# DC_DC.net
KiCad netlist of a schematic drawn in Altium Designer
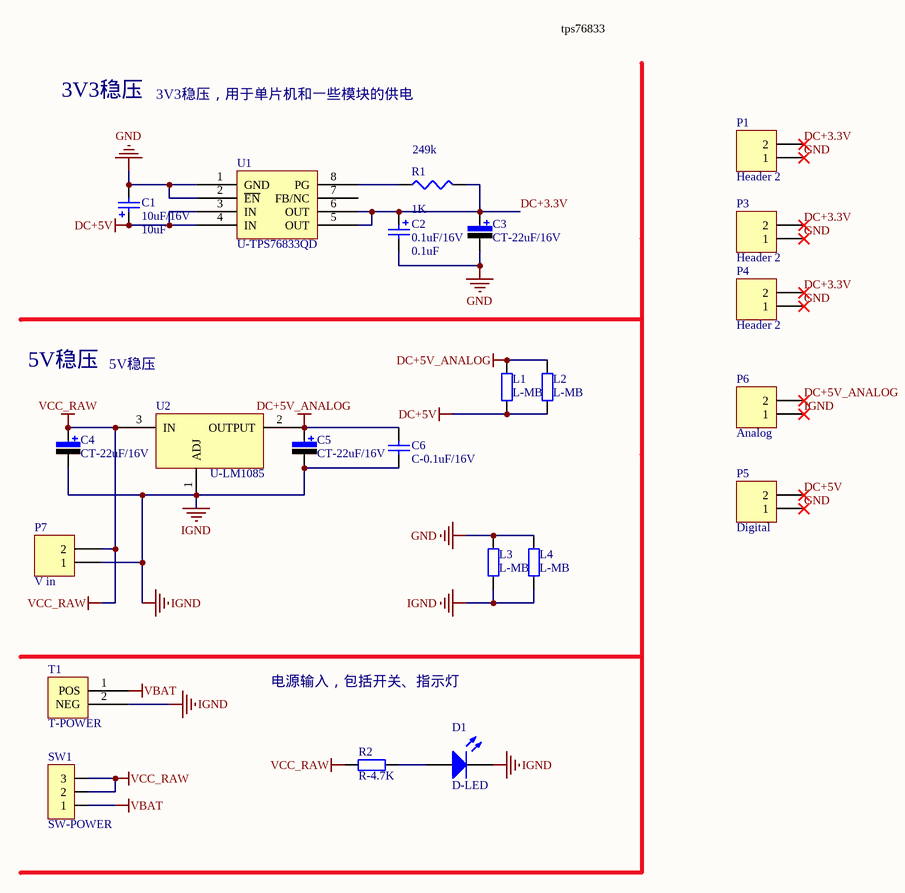
[diagram p0: DC_DC.SchDoc]

(export (version "E")
  (design (tool "Eeschema 10.0.6"))
  (components
    (comp (ref "C1")
      (value "10uF/16V")
      (footprint "CAP-1206")
      (description "Polarized Capacitor (Axial)")
      (fields (field (name "ALTIUM_VALUE") "10uF") (field (name "PUBLISHER") "Altium Limited"))
      (libsource (lib "Miscellaneous Devices") (part "Cap Pol2"))
    )
    (comp (ref "C2")
      (value "0.1uF/16V")
      (footprint "ZhiXingDoubleWing:CAP-1206")
      (description "Polarized Capacitor (Axial)")
      (fields (field (name "ALTIUM_VALUE") "0.1uF") (field (name "PUBLISHER") "Altium Limited"))
      (libsource (lib "Miscellaneous Devices") (part "Cap Pol2"))
    )
    (comp (ref "C3")
      (value "CT-22uF/16V")
      (footprint "CAP-3528")
      (description "钽电容")
      (fields (field (name "PUBLISHER") "Altium Limited"))
      (libsource (lib "Miscellaneous Devices") (part "Cap-Pol-A"))
    )
    (comp (ref "C4")
      (value "CT-22uF/16V")
      (footprint "CAP-3528")
      (description "钽电容")
      (fields (field (name "PUBLISHER") "Altium Limited"))
      (libsource (lib "fszhang") (part "Cap-Pol-A"))
    )
    (comp (ref "C5")
      (value "CT-22uF/16V")
      (footprint "CAP-3528")
      (description "钽电容")
      (fields (field (name "PUBLISHER") "Altium Limited"))
      (libsource (lib "fszhang") (part "Cap-Pol-A"))
    )
    (comp (ref "C6")
      (value "C-0.1uF/16V")
      (footprint "0603-1")
      (description "Capacitor")
      (fields (field (name "PUBLISHER") "Altium Limited"))
      (libsource (lib "Miscellaneous Devices") (part "Cap"))
    )
    (comp (ref "D1")
      (value "D-LED")
      (footprint "0603-1")
      (description "Typical RED, GREEN, YELLOW, AMBER GaAs LED")
      (fields (field (name "PUBLISHER") "Altium Limited"))
      (libsource (lib "FREESCALE") (part "LED2"))
    )
    (comp (ref "L1")
      (value "L-MB")
      (footprint "0603-1")
      (description "Resistor")
      (fields (field (name "PUBLISHER") "Altium Limited"))
      (libsource (lib "2014-SmartCar-DianCi(V4.0)") (part "Res2"))
    )
    (comp (ref "L2")
      (value "L-MB")
      (footprint "0603-1")
      (description "Resistor")
      (fields (field (name "PUBLISHER") "Altium Limited"))
      (libsource (lib "2014-SmartCar-DianCi(V4.0)") (part "Res2"))
    )
    (comp (ref "L3")
      (value "L-MB")
      (footprint "0603-1")
      (description "Resistor")
      (fields (field (name "PUBLISHER") "Altium Limited"))
      (libsource (lib "") (part "Res2_1"))
    )
    (comp (ref "L4")
      (value "L-MB")
      (footprint "0603-1")
      (description "Resistor")
      (fields (field (name "PUBLISHER") "Altium Limited"))
      (libsource (lib "") (part "Res2_1"))
    )
    (comp (ref "P1")
      (value "Header 2")
      (footprint "HDR1X2")
      (description "Header, 2-Pin")
      (fields (field (name "PUBLISHER") "Altium Limited"))
      (libsource (lib "Miscellaneous Connectors") (part "Header 2"))
    )
    (comp (ref "P3")
      (value "Header 2")
      (footprint "HDR1X2")
      (description "Header, 2-Pin")
      (fields (field (name "PUBLISHER") "Altium Limited"))
      (libsource (lib "Miscellaneous Connectors") (part "Header 2"))
    )
    (comp (ref "P4")
      (value "Header 2")
      (footprint "HDR1X2")
      (description "Header, 2-Pin")
      (fields (field (name "PUBLISHER") "Altium Limited"))
      (libsource (lib "Miscellaneous Connectors") (part "Header 2"))
    )
    (comp (ref "P5")
      (value "Digital")
      (footprint "HDR1X2")
      (description "Header, 2-Pin")
      (fields (field (name "PUBLISHER") "Altium Limited"))
      (libsource (lib "Miscellaneous Connectors") (part "Header 2"))
    )
    (comp (ref "P6")
      (value "Analog")
      (footprint "HDR1X2")
      (description "Header, 2-Pin")
      (fields (field (name "PUBLISHER") "Altium Limited"))
      (libsource (lib "Miscellaneous Connectors") (part "Header 2"))
    )
    (comp (ref "P7")
      (value "V in")
      (footprint "HDR1X2")
      (description "Header, 2-Pin")
      (fields (field (name "PUBLISHER") "Altium Limited"))
      (libsource (lib "Miscellaneous Connectors") (part "Header 2"))
    )
    (comp (ref "R1")
      (value "249k")
      (footprint "0603-1")
      (description "Resistor")
      (fields (field (name "ALTIUM_VALUE") "1K") (field (name "PUBLISHER") "Altium Limited"))
      (libsource (lib "Miscellaneous Devices") (part "Res3"))
    )
    (comp (ref "R2")
      (value "R-4.7K")
      (footprint "0603-1")
      (description "Resistor")
      (fields (field (name "PUBLISHER") "Altium Limited"))
      (libsource (lib "Miscellaneous Devices") (part "Res2"))
    )
    (comp (ref "SW1")
      (value "SW-POWER")
      (footprint "SWITCH_A4")
      (libsource (lib "FREESCALE") (part "大三端电源开关"))
    )
    (comp (ref "T1") (value "T-POWER") (footprint "PWR_HDR") (libsource (lib "fszhang") (part "PWR_HDR")))
    (comp (ref "U1") (value "U-TPS76833QD") (footprint "SOIC8") (libsource (lib "fszhang") (part "TPS76850")))
    (comp (ref "U2") (value "U-LM1085") (footprint "TO263-3") (libsource (lib "fszhang") (part "LM1085")))
  )
  (nets
    (net (code "1") (name "/DC+3.3V") (class "Default")
      (node (ref "C2") (pin "1") (pinfunction "1_1") (pintype "passive"))
      (node (ref "C3") (pin "1") (pinfunction "1_1") (pintype "passive"))
      (node (ref "P1") (pin "2") (pinfunction "2_2") (pintype "passive"))
      (node (ref "P3") (pin "2") (pinfunction "2_2") (pintype "passive"))
      (node (ref "P4") (pin "2") (pinfunction "2_2") (pintype "passive"))
      (node (ref "R1") (pin "2") (pinfunction "2_2") (pintype "passive"))
      (node (ref "U1") (pin "5") (pinfunction "OUT_5") (pintype "passive"))
      (node (ref "U1") (pin "6") (pinfunction "OUT_6") (pintype "passive"))
    )
    (net (code "2") (name "DC+5V") (class "Default")
      (node (ref "C1") (pin "1") (pinfunction "1_1") (pintype "passive"))
      (node (ref "L1") (pin "1") (pinfunction "1_1") (pintype "passive"))
      (node (ref "L2") (pin "1") (pinfunction "1_1") (pintype "passive"))
      (node (ref "P5") (pin "2") (pinfunction "2_2") (pintype "passive"))
      (node (ref "U1") (pin "3") (pinfunction "IN_3") (pintype "passive"))
      (node (ref "U1") (pin "4") (pinfunction "IN_4") (pintype "passive"))
    )
    (net (code "3") (name "DC+5V_ANALOG") (class "Default")
      (node (ref "C5") (pin "1") (pinfunction "1_1") (pintype "passive"))
      (node (ref "C6") (pin "2") (pinfunction "2_2") (pintype "passive"))
      (node (ref "L1") (pin "2") (pinfunction "2_2") (pintype "passive"))
      (node (ref "L2") (pin "2") (pinfunction "2_2") (pintype "passive"))
      (node (ref "P6") (pin "2") (pinfunction "2_2") (pintype "passive"))
      (node (ref "U2") (pin "2") (pinfunction "OUTPUT_2") (pintype "passive"))
    )
    (net (code "4") (name "GND") (class "Default")
      (node (ref "C1") (pin "2") (pinfunction "2_2") (pintype "passive"))
      (node (ref "C2") (pin "2") (pinfunction "2_2") (pintype "passive"))
      (node (ref "C3") (pin "2") (pinfunction "2_2") (pintype "passive"))
      (node (ref "L3") (pin "1") (pinfunction "1_1") (pintype "passive"))
      (node (ref "L4") (pin "1") (pinfunction "1_1") (pintype "passive"))
      (node (ref "P1") (pin "1") (pinfunction "1_1") (pintype "passive"))
      (node (ref "P3") (pin "1") (pinfunction "1_1") (pintype "passive"))
      (node (ref "P4") (pin "1") (pinfunction "1_1") (pintype "passive"))
      (node (ref "P5") (pin "1") (pinfunction "1_1") (pintype "passive"))
      (node (ref "U1") (pin "1") (pinfunction "GND_1") (pintype "passive"))
      (node (ref "U1") (pin "2") (pinfunction "~{EN}_2") (pintype "passive"))
    )
    (net (code "5") (name "IGND") (class "Default")
      (node (ref "C4") (pin "2") (pinfunction "2_2") (pintype "passive"))
      (node (ref "C5") (pin "2") (pinfunction "2_2") (pintype "passive"))
      (node (ref "C6") (pin "1") (pinfunction "1_1") (pintype "passive"))
      (node (ref "D1") (pin "2") (pinfunction "K_2") (pintype "passive"))
      (node (ref "L3") (pin "2") (pinfunction "2_2") (pintype "passive"))
      (node (ref "L4") (pin "2") (pinfunction "2_2") (pintype "passive"))
      (node (ref "P6") (pin "1") (pinfunction "1_1") (pintype "passive"))
      (node (ref "P7") (pin "1") (pinfunction "1_1") (pintype "passive"))
      (node (ref "T1") (pin "2") (pinfunction "NEG_2") (pintype "passive"))
      (node (ref "U2") (pin "1") (pinfunction "ADJ_1") (pintype "passive"))
    )
    (net (code "6") (name "Net-(D1-A)") (class "Default")
      (node (ref "D1") (pin "1") (pinfunction "A_1") (pintype "passive"))
      (node (ref "R2") (pin "1") (pinfunction "1_1") (pintype "passive"))
    )
    (net (code "7") (name "Net-(U1-PG)") (class "Default")
      (node (ref "R1") (pin "1") (pinfunction "1_1") (pintype "passive"))
      (node (ref "U1") (pin "8") (pinfunction "PG_8") (pintype "passive"))
    )
    (net (code "8") (name "VBAT") (class "Default")
      (node (ref "SW1") (pin "1") (pinfunction "1_1") (pintype "passive"))
      (node (ref "T1") (pin "1") (pinfunction "POS_1") (pintype "passive"))
    )
    (net (code "9") (name "VCC_RAW") (class "Default")
      (node (ref "C4") (pin "1") (pinfunction "1_1") (pintype "passive"))
      (node (ref "P7") (pin "2") (pinfunction "2_2") (pintype "passive"))
      (node (ref "R2") (pin "2") (pinfunction "2_2") (pintype "passive"))
      (node (ref "SW1") (pin "2") (pinfunction "2_2") (pintype "passive"))
      (node (ref "SW1") (pin "3") (pinfunction "3_3") (pintype "passive"))
      (node (ref "U2") (pin "3") (pinfunction "IN_3") (pintype "passive"))
    )
    (net (code "10") (name "unconnected-(U1-FB{slash}NC-Pad7)") (class "Default")
      (node (ref "U1") (pin "7") (pinfunction "FB/NC_7") (pintype "passive"))
    )
  )
)
